# LED_driver.net
KiCad netlist of a schematic drawn in Altium Designer
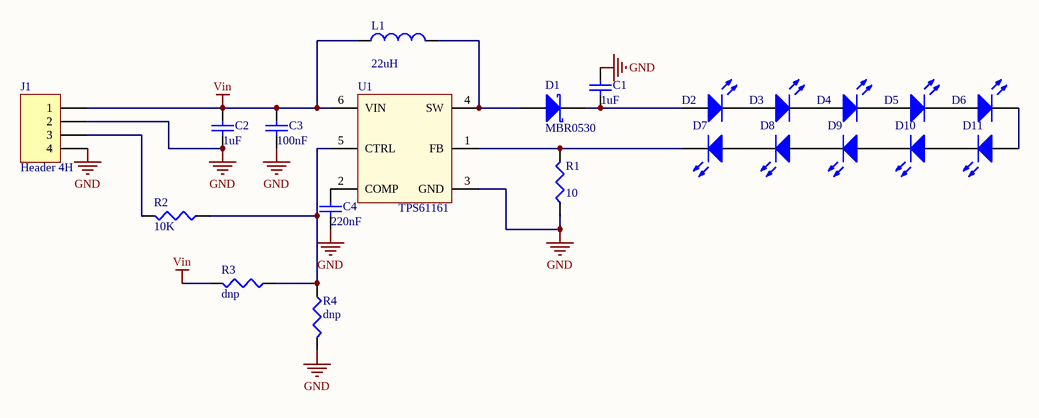
[diagram p0: LED_driver.SchDoc]

(export (version "E")
  (design (tool "Eeschema 10.0.6"))
  (components
    (comp (ref "C1")
      (value "1uF")
      (footprint "C0805")
      (description "Capacitor (Semiconductor SIM Model)")
      (fields (field (name "Comment") "Cap Semi") (field (name "PUBLISHER") "Altium Limited"))
      (libsource (lib "Miscellaneous Devices") (part "Cap Semi"))
    )
    (comp (ref "C2")
      (value "1uF")
      (footprint "C0805")
      (description "Capacitor (Semiconductor SIM Model)")
      (fields (field (name "Comment") "Cap Semi") (field (name "PUBLISHER") "Altium Limited"))
      (libsource (lib "Miscellaneous Devices") (part "Cap Semi"))
    )
    (comp (ref "C3")
      (value "100nF")
      (footprint "C0805")
      (description "Capacitor (Semiconductor SIM Model)")
      (fields (field (name "Comment") "Cap Semi") (field (name "PUBLISHER") "Altium Limited"))
      (libsource (lib "Miscellaneous Devices") (part "Cap Semi"))
    )
    (comp (ref "C4")
      (value "220nF")
      (footprint "C0805")
      (description "Capacitor (Semiconductor SIM Model)")
      (fields (field (name "Comment") "Cap Semi") (field (name "PUBLISHER") "Altium Limited"))
      (libsource (lib "Miscellaneous Devices") (part "Cap Semi"))
    )
    (comp (ref "D1")
      (value "MBR0530")
      (footprint "SOD_123")
      (description "Schottky Diode")
      (fields (field (name "PUBLISHER") "Altium Limited"))
      (libsource (lib "Miscellaneous Devices") (part "D Schottky"))
    )
    (comp (ref "D2")
      (value "LED2")
      (footprint "LED_0805")
      (description "Typical RED, GREEN, YELLOW, AMBER GaAs LED")
      (fields (field (name "PUBLISHER") "Altium Limited"))
      (libsource (lib "Miscellaneous Devices") (part "LED2"))
    )
    (comp (ref "D3")
      (value "LED2")
      (footprint "LED_0805")
      (description "Typical RED, GREEN, YELLOW, AMBER GaAs LED")
      (fields (field (name "PUBLISHER") "Altium Limited"))
      (libsource (lib "Miscellaneous Devices") (part "LED2"))
    )
    (comp (ref "D4")
      (value "LED2")
      (footprint "LED_0805")
      (description "Typical RED, GREEN, YELLOW, AMBER GaAs LED")
      (fields (field (name "PUBLISHER") "Altium Limited"))
      (libsource (lib "Miscellaneous Devices") (part "LED2"))
    )
    (comp (ref "D5")
      (value "LED2")
      (footprint "LED_0805")
      (description "Typical RED, GREEN, YELLOW, AMBER GaAs LED")
      (fields (field (name "PUBLISHER") "Altium Limited"))
      (libsource (lib "Miscellaneous Devices") (part "LED2"))
    )
    (comp (ref "D6")
      (value "LED2")
      (footprint "LED_0805")
      (description "Typical RED, GREEN, YELLOW, AMBER GaAs LED")
      (fields (field (name "PUBLISHER") "Altium Limited"))
      (libsource (lib "Miscellaneous Devices") (part "LED2"))
    )
    (comp (ref "D7")
      (value "LED2")
      (footprint "LED_0805")
      (description "Typical RED, GREEN, YELLOW, AMBER GaAs LED")
      (fields (field (name "PUBLISHER") "Altium Limited"))
      (libsource (lib "Miscellaneous Devices") (part "LED2"))
    )
    (comp (ref "D8")
      (value "LED2")
      (footprint "LED_0805")
      (description "Typical RED, GREEN, YELLOW, AMBER GaAs LED")
      (fields (field (name "PUBLISHER") "Altium Limited"))
      (libsource (lib "Miscellaneous Devices") (part "LED2"))
    )
    (comp (ref "D9")
      (value "LED2")
      (footprint "LED_0805")
      (description "Typical RED, GREEN, YELLOW, AMBER GaAs LED")
      (fields (field (name "PUBLISHER") "Altium Limited"))
      (libsource (lib "Miscellaneous Devices") (part "LED2"))
    )
    (comp (ref "D10")
      (value "LED2")
      (footprint "LED_0805")
      (description "Typical RED, GREEN, YELLOW, AMBER GaAs LED")
      (fields (field (name "PUBLISHER") "Altium Limited"))
      (libsource (lib "Miscellaneous Devices") (part "LED2"))
    )
    (comp (ref "D11")
      (value "LED2")
      (footprint "LED_0805")
      (description "Typical RED, GREEN, YELLOW, AMBER GaAs LED")
      (fields (field (name "PUBLISHER") "Altium Limited"))
      (libsource (lib "Miscellaneous Devices") (part "LED2"))
    )
    (comp (ref "J1")
      (value "Header 4H")
      (footprint "HDR2X2")
      (description "Header, 4-Pin, Right Angle")
      (fields (field (name "PUBLISHER") "Altium Limited"))
      (libsource (lib "Miscellaneous Connectors") (part "Header 4H"))
    )
    (comp (ref "L1")
      (value "22uH")
      (footprint "5020")
      (description "Inductor")
      (fields (field (name "PUBLISHER") "Altium Limited"))
      (libsource (lib "Miscellaneous Devices") (part "Inductor"))
    )
    (comp (ref "R1")
      (value "10")
      (footprint "J1-0603")
      (description "Resistor")
      (fields (field (name "Comment") "Res3") (field (name "PUBLISHER") "Altium Limited"))
      (libsource (lib "Miscellaneous Devices") (part "Res3"))
    )
    (comp (ref "R2")
      (value "10K")
      (footprint "J1-0603")
      (description "Resistor")
      (fields (field (name "Comment") "Res3") (field (name "PUBLISHER") "Altium Limited"))
      (libsource (lib "Miscellaneous Devices") (part "Res3"))
    )
    (comp (ref "R3")
      (value "dnp")
      (footprint "J1-0603")
      (description "Resistor")
      (fields (field (name "Comment") "Res3") (field (name "PUBLISHER") "Altium Limited"))
      (libsource (lib "Miscellaneous Devices") (part "Res3"))
    )
    (comp (ref "R4")
      (value "dnp")
      (footprint "J1-0603")
      (description "Resistor")
      (fields (field (name "Comment") "Res3") (field (name "PUBLISHER") "Altium Limited"))
      (libsource (lib "Miscellaneous Devices") (part "Res3"))
    )
    (comp (ref "U1") (value "TPS61161") (footprint "SON6") (libsource (lib "led_driver") (part "TPS61161")))
  )
  (nets
    (net (code "1") (name "GND") (class "Default")
      (node (ref "C1") (pin "2") (pinfunction "2_2") (pintype "passive"))
      (node (ref "C2") (pin "1") (pinfunction "1_1") (pintype "passive"))
      (node (ref "C3") (pin "1") (pinfunction "1_1") (pintype "passive"))
      (node (ref "C4") (pin "1") (pinfunction "1_1") (pintype "passive"))
      (node (ref "J1") (pin "2") (pinfunction "2_2") (pintype "passive"))
      (node (ref "J1") (pin "4") (pinfunction "4_4") (pintype "passive"))
      (node (ref "R1") (pin "1") (pinfunction "1_1") (pintype "passive"))
      (node (ref "R4") (pin "2") (pinfunction "2_2") (pintype "passive"))
      (node (ref "U1") (pin "3") (pinfunction "GND_3") (pintype "passive"))
    )
    (net (code "2") (name "Net-(D1-A)") (class "Default")
      (node (ref "D1") (pin "1") (pinfunction "A_1") (pintype "passive"))
      (node (ref "L1") (pin "2") (pinfunction "2_2") (pintype "passive"))
      (node (ref "U1") (pin "4") (pinfunction "SW_4") (pintype "passive"))
    )
    (net (code "3") (name "Net-(D1-K)") (class "Default")
      (node (ref "C1") (pin "1") (pinfunction "1_1") (pintype "passive"))
      (node (ref "D1") (pin "2") (pinfunction "K_2") (pintype "passive"))
      (node (ref "D2") (pin "1") (pinfunction "A_1") (pintype "passive"))
    )
    (net (code "4") (name "Net-(D2-K)") (class "Default")
      (node (ref "D2") (pin "2") (pinfunction "K_2") (pintype "passive"))
      (node (ref "D3") (pin "1") (pinfunction "A_1") (pintype "passive"))
    )
    (net (code "5") (name "Net-(D3-K)") (class "Default")
      (node (ref "D3") (pin "2") (pinfunction "K_2") (pintype "passive"))
      (node (ref "D4") (pin "1") (pinfunction "A_1") (pintype "passive"))
    )
    (net (code "6") (name "Net-(D4-K)") (class "Default")
      (node (ref "D4") (pin "2") (pinfunction "K_2") (pintype "passive"))
      (node (ref "D5") (pin "1") (pinfunction "A_1") (pintype "passive"))
    )
    (net (code "7") (name "Net-(D5-K)") (class "Default")
      (node (ref "D5") (pin "2") (pinfunction "K_2") (pintype "passive"))
      (node (ref "D6") (pin "1") (pinfunction "A_1") (pintype "passive"))
    )
    (net (code "8") (name "Net-(D7-A)") (class "Default")
      (node (ref "D7") (pin "1") (pinfunction "A_1") (pintype "passive"))
      (node (ref "D8") (pin "2") (pinfunction "K_2") (pintype "passive"))
    )
    (net (code "9") (name "Net-(D7-K)") (class "Default")
      (node (ref "D7") (pin "2") (pinfunction "K_2") (pintype "passive"))
      (node (ref "R1") (pin "2") (pinfunction "2_2") (pintype "passive"))
      (node (ref "U1") (pin "1") (pinfunction "FB_1") (pintype "passive"))
    )
    (net (code "10") (name "Net-(D8-A)") (class "Default")
      (node (ref "D8") (pin "1") (pinfunction "A_1") (pintype "passive"))
      (node (ref "D9") (pin "2") (pinfunction "K_2") (pintype "passive"))
    )
    (net (code "11") (name "Net-(D10-A)") (class "Default")
      (node (ref "D10") (pin "1") (pinfunction "A_1") (pintype "passive"))
      (node (ref "D11") (pin "2") (pinfunction "K_2") (pintype "passive"))
    )
    (net (code "12") (name "Net-(D10-K)") (class "Default")
      (node (ref "D10") (pin "2") (pinfunction "K_2") (pintype "passive"))
      (node (ref "D9") (pin "1") (pinfunction "A_1") (pintype "passive"))
    )
    (net (code "13") (name "Net-(D11-A)") (class "Default")
      (node (ref "D11") (pin "1") (pinfunction "A_1") (pintype "passive"))
      (node (ref "D6") (pin "2") (pinfunction "K_2") (pintype "passive"))
    )
    (net (code "14") (name "Net-(J1-Pad3)") (class "Default")
      (node (ref "J1") (pin "3") (pinfunction "3_3") (pintype "passive"))
      (node (ref "R2") (pin "2") (pinfunction "2_2") (pintype "passive"))
    )
    (net (code "15") (name "Net-(U1-COMP)") (class "Default")
      (node (ref "C4") (pin "2") (pinfunction "2_2") (pintype "passive"))
      (node (ref "U1") (pin "2") (pinfunction "COMP_2") (pintype "passive"))
    )
    (net (code "16") (name "Net-(U1-CTRL)") (class "Default")
      (node (ref "R2") (pin "1") (pinfunction "1_1") (pintype "passive"))
      (node (ref "R3") (pin "1") (pinfunction "1_1") (pintype "passive"))
      (node (ref "R4") (pin "1") (pinfunction "1_1") (pintype "passive"))
      (node (ref "U1") (pin "5") (pinfunction "CTRL_5") (pintype "passive"))
    )
    (net (code "17") (name "Vin") (class "Default")
      (node (ref "C2") (pin "2") (pinfunction "2_2") (pintype "passive"))
      (node (ref "C3") (pin "2") (pinfunction "2_2") (pintype "passive"))
      (node (ref "J1") (pin "1") (pinfunction "1_1") (pintype "passive"))
      (node (ref "L1") (pin "1") (pinfunction "1_1") (pintype "passive"))
      (node (ref "R3") (pin "2") (pinfunction "2_2") (pintype "passive"))
      (node (ref "U1") (pin "6") (pinfunction "VIN_6") (pintype "passive"))
    )
  )
)
